# USB_Downloader.net
KiCad netlist of a schematic drawn in Altium Designer
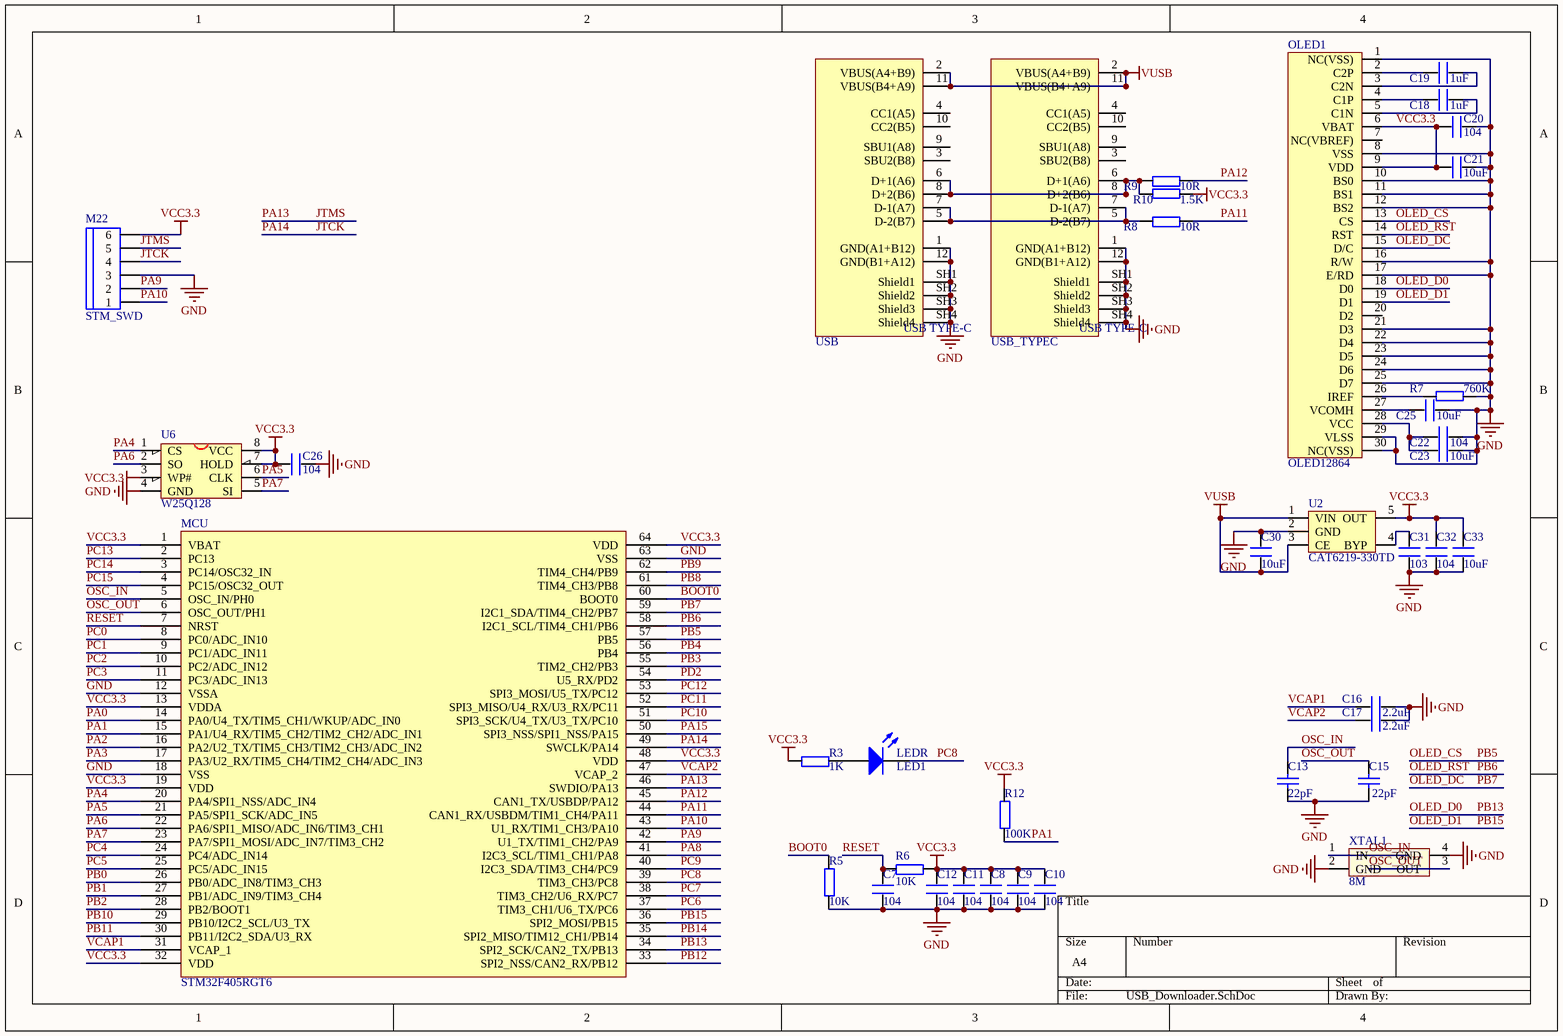
[diagram p0: USB_Downloader.SchDoc]

(export (version "E")
  (design (tool "Eeschema 10.0.6"))
  (components
    (comp (ref "C7")
      (value "104")
      (footprint "C 0603_L")
      (libsource (lib "WarShip V3 STM32103封装库") (part "C"))
    )
    (comp (ref "C8")
      (value "104")
      (footprint "C 0603_L")
      (libsource (lib "WarShip V3 STM32103封装库") (part "C"))
    )
    (comp (ref "C9")
      (value "104")
      (footprint "C 0603_L")
      (libsource (lib "WarShip V3 STM32103封装库") (part "C"))
    )
    (comp (ref "C10")
      (value "104")
      (footprint "C 0603_L")
      (libsource (lib "WarShip V3 STM32103封装库") (part "C"))
    )
    (comp (ref "C11")
      (value "104")
      (footprint "C 0603_L")
      (libsource (lib "WarShip V3 STM32103封装库") (part "C"))
    )
    (comp (ref "C12")
      (value "104")
      (footprint "C 0603_L")
      (libsource (lib "WarShip V3 STM32103封装库") (part "C"))
    )
    (comp (ref "C13") (value "22pF") (footprint "C 0603_L") (libsource (lib "L476") (part "CAP")))
    (comp (ref "C15") (value "22pF") (footprint "C 0603_L") (libsource (lib "L476") (part "CAP")))
    (comp (ref "C16")
      (value "2.2uF")
      (footprint "C 0603_L")
      (libsource (lib "WarShip V3 STM32103封装库") (part "C"))
    )
    (comp (ref "C17")
      (value "2.2uF")
      (footprint "C 0603_L")
      (libsource (lib "WarShip V3 STM32103封装库") (part "C"))
    )
    (comp (ref "C18")
      (value "1uF")
      (footprint "C 0603_L")
      (libsource (lib "WarShip V3 STM32103封装库") (part "C"))
    )
    (comp (ref "C19")
      (value "1uF")
      (footprint "C 0603_L")
      (libsource (lib "WarShip V3 STM32103封装库") (part "C"))
    )
    (comp (ref "C20")
      (value "104")
      (footprint "C 0603_L")
      (libsource (lib "WarShip V3 STM32103封装库") (part "C"))
    )
    (comp (ref "C21")
      (value "10uF")
      (footprint "C 0603_L")
      (libsource (lib "WarShip V3 STM32103封装库") (part "C"))
    )
    (comp (ref "C22")
      (value "104")
      (footprint "C 0603_L")
      (libsource (lib "WarShip V3 STM32103封装库") (part "C"))
    )
    (comp (ref "C23")
      (value "10uF")
      (footprint "C 0603_L")
      (libsource (lib "WarShip V3 STM32103封装库") (part "C"))
    )
    (comp (ref "C25")
      (value "10uF")
      (footprint "C 0603_L")
      (libsource (lib "WarShip V3 STM32103封装库") (part "C"))
    )
    (comp (ref "C26")
      (value "104")
      (footprint "C 0603_L")
      (libsource (lib "WarShip V3 STM32103封装库") (part "C"))
    )
    (comp (ref "C30")
      (value "10uF")
      (footprint "C 0603_L")
      (libsource (lib "WarShip V3 STM32103封装库") (part "C"))
    )
    (comp (ref "C31")
      (value "103")
      (footprint "C 0603_L")
      (libsource (lib "WarShip V3 STM32103封装库") (part "C"))
    )
    (comp (ref "C32")
      (value "104")
      (footprint "C 0603_L")
      (libsource (lib "WarShip V3 STM32103封装库") (part "C"))
    )
    (comp (ref "C33")
      (value "10uF")
      (footprint "C 0603_L")
      (libsource (lib "WarShip V3 STM32103封装库") (part "C"))
    )
    (comp (ref "LEDR")
      (value "LED1")
      (footprint "LED 0805B")
      (description "Typical RED, GREEN, YELLOW, AMBER GaAs LED")
      (fields (field (name "PUBLISHER") "Altium Limited"))
      (libsource (lib "阿波罗STM32F4&F7底板封装库") (part "LED2"))
    )
    (comp (ref "M22") (value "STM_SWD") (footprint "SH1.0-6P") (libsource (lib "MiniFly ") (part "HEAD6")))
    (comp (ref "MCU")
      (value "STM32F405RGT6")
      (footprint "LQFP64 10X10_L")
      (description "Flaah:256/RAM:48/IO:51")
      (libsource (lib "ATKF405 V1.1") (part "STM32F405RGT6"))
    )
    (comp (ref "OLED1")
      (value "OLED12864")
      (footprint "OLED_0.96")
      (libsource (lib "OLED模块封装库") (part "OLED12864"))
    )
    (comp (ref "R3")
      (value "1K")
      (footprint "R 0603_L")
      (libsource (lib "WarShip V3 STM32103封装库") (part "R"))
    )
    (comp (ref "R5")
      (value "10K")
      (footprint "R 0603_L")
      (libsource (lib "WarShip V3 STM32103封装库") (part "R"))
    )
    (comp (ref "R6")
      (value "10K")
      (footprint "R 0603_L")
      (libsource (lib "WarShip V3 STM32103封装库") (part "R"))
    )
    (comp (ref "R7")
      (value "760K")
      (footprint "R 0603_L")
      (libsource (lib "WarShip V3 STM32103封装库") (part "R"))
    )
    (comp (ref "R8")
      (value "10R")
      (footprint "R 0603_L")
      (libsource (lib "WarShip V3 STM32103封装库") (part "R"))
    )
    (comp (ref "R9")
      (value "10R")
      (footprint "R 0603_L")
      (libsource (lib "WarShip V3 STM32103封装库") (part "R"))
    )
    (comp (ref "R10")
      (value "1.5K")
      (footprint "R 0603_L")
      (libsource (lib "WarShip V3 STM32103封装库") (part "R"))
    )
    (comp (ref "R12")
      (value "100K")
      (footprint "R 0603_L")
      (libsource (lib "WarShip V3 STM32103封装库") (part "R"))
    )
    (comp (ref "U2")
      (value "CAT6219-330TD")
      (footprint "SOT23-5L")
      (description "3.3V 500mA LDO")
      (libsource (lib "STM32H743核心板封装库") (part "CAT6219-330TD"))
    )
    (comp (ref "U6")
      (value "W25Q128")
      (footprint "SOP8W_L")
      (description "W25X16;SST25VF016;MX25L1605")
      (libsource (lib "WarShip V3 STM32103封装库") (part "W25X16"))
    )
    (comp (ref "USB")
      (value "USB TypeC")
      (footprint "USB Type-C")
      (description "12P TypeC 母座")
      (libsource (lib "ESP32_Weather") (part "USB Type-C"))
    )
    (comp (ref "USB_TYPEC")
      (value "USB TypeC")
      (footprint "USB Type-C")
      (description "12P TypeC 母座")
      (libsource (lib "ESP32_Weather") (part "USB Type-C"))
    )
    (comp (ref "XTAL1")
      (value "8M")
      (footprint "XTAL3225   无源")
      (description "无源贴片晶振")
      (libsource (lib "REMOTOR") (part "XTAL-无源贴片"))
    )
  )
  (nets
    (net (code "1") (name "/BOOT0") (class "Default")
      (node (ref "MCU") (pin "60") (pinfunction "BOOT0_60") (pintype "passive"))
      (node (ref "R5") (pin "2") (pintype "passive"))
    )
    (net (code "2") (name "/JTCK") (class "Default")
      (node (ref "M22") (pin "4") (pinfunction "4_4") (pintype "passive"))
      (node (ref "MCU") (pin "49") (pinfunction "SWCLK/PA14_49") (pintype "passive"))
    )
    (net (code "3") (name "/JTMS") (class "Default")
      (node (ref "M22") (pin "5") (pinfunction "5_5") (pintype "passive"))
      (node (ref "MCU") (pin "46") (pinfunction "SWDIO/PA13_46") (pintype "passive"))
    )
    (net (code "4") (name "/OLED_CS") (class "Default")
      (node (ref "MCU") (pin "57") (pinfunction "PB5_57") (pintype "passive"))
      (node (ref "OLED1") (pin "13") (pinfunction "CS_13") (pintype "passive"))
    )
    (net (code "5") (name "/OLED_D0") (class "Default")
      (node (ref "MCU") (pin "34") (pinfunction "SPI2_SCK/CAN2_TX/PB13_34") (pintype "passive"))
      (node (ref "OLED1") (pin "18") (pinfunction "D0_18") (pintype "passive"))
    )
    (net (code "6") (name "/OLED_D1") (class "Default")
      (node (ref "MCU") (pin "36") (pinfunction "SPI2_MOSI/PB15_36") (pintype "passive"))
      (node (ref "OLED1") (pin "19") (pinfunction "D1_19") (pintype "passive"))
    )
    (net (code "7") (name "/OLED_DC") (class "Default")
      (node (ref "MCU") (pin "59") (pinfunction "I2C1_SDA/TIM4_CH2/PB7_59") (pintype "passive"))
      (node (ref "OLED1") (pin "15") (pinfunction "D/C_15") (pintype "passive"))
    )
    (net (code "8") (name "/OLED_RST") (class "Default")
      (node (ref "MCU") (pin "58") (pinfunction "I2C1_SCL/TIM4_CH1/PB6_58") (pintype "passive"))
      (node (ref "OLED1") (pin "14") (pinfunction "RST_14") (pintype "passive"))
    )
    (net (code "9") (name "/OSC_IN") (class "Default")
      (node (ref "C13") (pin "2") (pinfunction "2_2") (pintype "passive"))
      (node (ref "MCU") (pin "5") (pinfunction "OSC_IN/PH0_5") (pintype "passive"))
      (node (ref "XTAL1") (pin "1") (pinfunction "IN_1") (pintype "passive"))
    )
    (net (code "10") (name "/OSC_OUT") (class "Default")
      (node (ref "C15") (pin "2") (pinfunction "2_2") (pintype "passive"))
      (node (ref "MCU") (pin "6") (pinfunction "OSC_OUT/PH1_6") (pintype "passive"))
      (node (ref "XTAL1") (pin "3") (pinfunction "OUT_3") (pintype "passive"))
    )
    (net (code "11") (name "/PA0") (class "Default")
      (node (ref "MCU") (pin "14") (pinfunction "PA0/U4_TX/TIM5_CH1/WKUP/ADC_IN0_14") (pintype "passive"))
    )
    (net (code "12") (name "/PA1") (class "Default")
      (node (ref "MCU") (pin "15") (pinfunction "PA1/U4_RX/TIM5_CH2/TIM2_CH2/ADC_IN1_15") (pintype "passive"))
      (node (ref "R12") (pin "1") (pintype "passive"))
    )
    (net (code "13") (name "/PA2") (class "Default")
      (node (ref "MCU") (pin "16") (pinfunction "PA2/U2_TX/TIM5_CH3/TIM2_CH3/ADC_IN2_16") (pintype "passive"))
    )
    (net (code "14") (name "/PA3") (class "Default")
      (node (ref "MCU") (pin "17") (pinfunction "PA3/U2_RX/TIM5_CH4/TIM2_CH4/ADC_IN3_17") (pintype "passive"))
    )
    (net (code "15") (name "/PA4") (class "Default")
      (node (ref "MCU") (pin "20") (pinfunction "PA4/SPI1_NSS/ADC_IN4_20") (pintype "passive"))
      (node (ref "U6") (pin "1") (pinfunction "CS_1") (pintype "passive"))
    )
    (net (code "16") (name "/PA5") (class "Default")
      (node (ref "MCU") (pin "21") (pinfunction "PA5/SPI1_SCK/ADC_IN5_21") (pintype "passive"))
      (node (ref "U6") (pin "6") (pinfunction "CLK_6") (pintype "passive"))
    )
    (net (code "17") (name "/PA6") (class "Default")
      (node (ref "MCU") (pin "22") (pinfunction "PA6/SPI1_MISO/ADC_IN6/TIM3_CH1_22") (pintype "passive"))
      (node (ref "U6") (pin "2") (pinfunction "SO_2") (pintype "passive"))
    )
    (net (code "18") (name "/PA7") (class "Default")
      (node (ref "MCU") (pin "23") (pinfunction "PA7/SPI1_MOSI/ADC_IN7/TIM3_CH2_23") (pintype "passive"))
      (node (ref "U6") (pin "5") (pinfunction "SI_5") (pintype "passive"))
    )
    (net (code "19") (name "/PA8") (class "Default")
      (node (ref "MCU") (pin "41") (pinfunction "I2C3_SCL/TIM1_CH1/PA8_41") (pintype "passive"))
    )
    (net (code "20") (name "/PA9") (class "Default")
      (node (ref "M22") (pin "2") (pinfunction "2_2") (pintype "passive"))
      (node (ref "MCU") (pin "42") (pinfunction "U1_TX/TIM1_CH2/PA9_42") (pintype "passive"))
    )
    (net (code "21") (name "/PA10") (class "Default")
      (node (ref "M22") (pin "1") (pinfunction "1_1") (pintype "passive"))
      (node (ref "MCU") (pin "43") (pinfunction "U1_RX/TIM1_CH3/PA10_43") (pintype "passive"))
    )
    (net (code "22") (name "/PA11") (class "Default")
      (node (ref "MCU") (pin "44") (pinfunction "CAN1_RX/USBDM/TIM1_CH4/PA11_44") (pintype "passive"))
      (node (ref "R8") (pin "2") (pintype "passive"))
    )
    (net (code "23") (name "/PA12") (class "Default")
      (node (ref "MCU") (pin "45") (pinfunction "CAN1_TX/USBDP/PA12_45") (pintype "passive"))
      (node (ref "R9") (pin "2") (pintype "passive"))
    )
    (net (code "24") (name "/PA15") (class "Default")
      (node (ref "MCU") (pin "50") (pinfunction "SPI3_NSS/SPI1_NSS/PA15_50") (pintype "passive"))
    )
    (net (code "25") (name "/PB0") (class "Default")
      (node (ref "MCU") (pin "26") (pinfunction "PB0/ADC_IN8/TIM3_CH3_26") (pintype "passive"))
    )
    (net (code "26") (name "/PB1") (class "Default")
      (node (ref "MCU") (pin "27") (pinfunction "PB1/ADC_IN9/TIM3_CH4_27") (pintype "passive"))
    )
    (net (code "27") (name "/PB2") (class "Default")
      (node (ref "MCU") (pin "28") (pinfunction "PB2/BOOT1_28") (pintype "passive"))
    )
    (net (code "28") (name "/PB3") (class "Default")
      (node (ref "MCU") (pin "55") (pinfunction "TIM2_CH2/PB3_55") (pintype "passive"))
    )
    (net (code "29") (name "/PB4") (class "Default")
      (node (ref "MCU") (pin "56") (pinfunction "PB4_56") (pintype "passive"))
    )
    (net (code "30") (name "/PB8") (class "Default")
      (node (ref "MCU") (pin "61") (pinfunction "TIM4_CH3/PB8_61") (pintype "passive"))
    )
    (net (code "31") (name "/PB9") (class "Default")
      (node (ref "MCU") (pin "62") (pinfunction "TIM4_CH4/PB9_62") (pintype "passive"))
    )
    (net (code "32") (name "/PB10") (class "Default")
      (node (ref "MCU") (pin "29") (pinfunction "PB10/I2C2_SCL/U3_TX_29") (pintype "passive"))
    )
    (net (code "33") (name "/PB11") (class "Default")
      (node (ref "MCU") (pin "30") (pinfunction "PB11/I2C2_SDA/U3_RX_30") (pintype "passive"))
    )
    (net (code "34") (name "/PB12") (class "Default")
      (node (ref "MCU") (pin "33") (pinfunction "SPI2_NSS/CAN2_RX/PB12_33") (pintype "passive"))
    )
    (net (code "35") (name "/PB14") (class "Default")
      (node (ref "MCU") (pin "35") (pinfunction "SPI2_MISO/TIM12_CH1/PB14_35") (pintype "passive"))
    )
    (net (code "36") (name "/PC0") (class "Default")
      (node (ref "MCU") (pin "8") (pinfunction "PC0/ADC_IN10_8") (pintype "passive"))
    )
    (net (code "37") (name "/PC1") (class "Default")
      (node (ref "MCU") (pin "9") (pinfunction "PC1/ADC_IN11_9") (pintype "passive"))
    )
    (net (code "38") (name "/PC2") (class "Default")
      (node (ref "MCU") (pin "10") (pinfunction "PC2/ADC_IN12_10") (pintype "passive"))
    )
    (net (code "39") (name "/PC3") (class "Default")
      (node (ref "MCU") (pin "11") (pinfunction "PC3/ADC_IN13_11") (pintype "passive"))
    )
    (net (code "40") (name "/PC4") (class "Default")
      (node (ref "MCU") (pin "24") (pinfunction "PC4/ADC_IN14_24") (pintype "passive"))
    )
    (net (code "41") (name "/PC5") (class "Default")
      (node (ref "MCU") (pin "25") (pinfunction "PC5/ADC_IN15_25") (pintype "passive"))
    )
    (net (code "42") (name "/PC6") (class "Default")
      (node (ref "MCU") (pin "37") (pinfunction "TIM3_CH1/U6_TX/PC6_37") (pintype "passive"))
    )
    (net (code "43") (name "/PC7") (class "Default")
      (node (ref "MCU") (pin "38") (pinfunction "TIM3_CH2/U6_RX/PC7_38") (pintype "passive"))
    )
    (net (code "44") (name "/PC8") (class "Default")
      (node (ref "LEDR") (pin "2") (pinfunction "K_2") (pintype "passive"))
      (node (ref "MCU") (pin "39") (pinfunction "TIM3_CH3/PC8_39") (pintype "passive"))
    )
    (net (code "45") (name "/PC9") (class "Default")
      (node (ref "MCU") (pin "40") (pinfunction "I2C3_SDA/TIM3_CH4/PC9_40") (pintype "passive"))
    )
    (net (code "46") (name "/PC10") (class "Default")
      (node (ref "MCU") (pin "51") (pinfunction "SPI3_SCK/U4_TX/U3_TX/PC10_51") (pintype "passive"))
    )
    (net (code "47") (name "/PC11") (class "Default")
      (node (ref "MCU") (pin "52") (pinfunction "SPI3_MISO/U4_RX/U3_RX/PC11_52") (pintype "passive"))
    )
    (net (code "48") (name "/PC12") (class "Default")
      (node (ref "MCU") (pin "53") (pinfunction "SPI3_MOSI/U5_TX/PC12_53") (pintype "passive"))
    )
    (net (code "49") (name "/PC13") (class "Default")
      (node (ref "MCU") (pin "2") (pinfunction "PC13_2") (pintype "passive"))
    )
    (net (code "50") (name "/PC14") (class "Default")
      (node (ref "MCU") (pin "3") (pinfunction "PC14/OSC32_IN_3") (pintype "passive"))
    )
    (net (code "51") (name "/PC15") (class "Default")
      (node (ref "MCU") (pin "4") (pinfunction "PC15/OSC32_OUT_4") (pintype "passive"))
    )
    (net (code "52") (name "/PD2") (class "Default")
      (node (ref "MCU") (pin "54") (pinfunction "U5_RX/PD2_54") (pintype "passive"))
    )
    (net (code "53") (name "/RESET") (class "Default")
      (node (ref "C7") (pin "2") (pintype "passive"))
      (node (ref "MCU") (pin "7") (pinfunction "NRST_7") (pintype "passive"))
      (node (ref "R6") (pin "1") (pintype "passive"))
    )
    (net (code "54") (name "/VCAP1") (class "Default")
      (node (ref "C16") (pin "2") (pintype "passive"))
      (node (ref "MCU") (pin "31") (pinfunction "VCAP_1_31") (pintype "passive"))
    )
    (net (code "55") (name "/VCAP2") (class "Default")
      (node (ref "C17") (pin "2") (pintype "passive"))
      (node (ref "MCU") (pin "47") (pinfunction "VCAP_2_47") (pintype "passive"))
    )
    (net (code "56") (name "GND") (class "Default")
      (node (ref "C10") (pin "1") (pintype "passive"))
      (node (ref "C11") (pin "1") (pintype "passive"))
      (node (ref "C12") (pin "1") (pintype "passive"))
      (node (ref "C13") (pin "1") (pinfunction "1_1") (pintype "passive"))
      (node (ref "C15") (pin "1") (pinfunction "1_1") (pintype "passive"))
      (node (ref "C16") (pin "1") (pintype "passive"))
      (node (ref "C17") (pin "1") (pintype "passive"))
      (node (ref "C20") (pin "1") (pintype "passive"))
      (node (ref "C21") (pin "1") (pintype "passive"))
      (node (ref "C22") (pin "1") (pintype "passive"))
      (node (ref "C23") (pin "1") (pintype "passive"))
      (node (ref "C25") (pin "1") (pintype "passive"))
      (node (ref "C26") (pin "2") (pintype "passive"))
      (node (ref "C30") (pin "2") (pintype "passive"))
      (node (ref "C31") (pin "1") (pintype "passive"))
      (node (ref "C32") (pin "1") (pintype "passive"))
      (node (ref "C33") (pin "1") (pintype "passive"))
      (node (ref "C7") (pin "1") (pintype "passive"))
      (node (ref "C8") (pin "1") (pintype "passive"))
      (node (ref "C9") (pin "1") (pintype "passive"))
      (node (ref "M22") (pin "3") (pinfunction "3_3") (pintype "passive"))
      (node (ref "MCU") (pin "12") (pinfunction "VSSA_12") (pintype "passive"))
      (node (ref "MCU") (pin "18") (pinfunction "VSS_18") (pintype "passive"))
      (node (ref "MCU") (pin "63") (pinfunction "VSS_63") (pintype "passive"))
      (node (ref "OLED1") (pin "1") (pinfunction "NC(VSS)_1") (pintype "passive"))
      (node (ref "OLED1") (pin "10") (pinfunction "BS0_10") (pintype "passive"))
      (node (ref "OLED1") (pin "11") (pinfunction "BS1_11") (pintype "passive"))
      (node (ref "OLED1") (pin "12") (pinfunction "BS2_12") (pintype "passive"))
      (node (ref "OLED1") (pin "16") (pinfunction "R/W_16") (pintype "passive"))
      (node (ref "OLED1") (pin "17") (pinfunction "E/RD_17") (pintype "passive"))
      (node (ref "OLED1") (pin "21") (pinfunction "D3_21") (pintype "passive"))
      (node (ref "OLED1") (pin "22") (pinfunction "D4_22") (pintype "passive"))
      (node (ref "OLED1") (pin "23") (pinfunction "D5_23") (pintype "passive"))
      (node (ref "OLED1") (pin "24") (pinfunction "D6_24") (pintype "passive"))
      (node (ref "OLED1") (pin "25") (pinfunction "D7_25") (pintype "passive"))
      (node (ref "OLED1") (pin "29") (pinfunction "VLSS_29") (pintype "passive"))
      (node (ref "OLED1") (pin "30") (pinfunction "NC(VSS)_30") (pintype "passive"))
      (node (ref "OLED1") (pin "8") (pinfunction "VSS_8") (pintype "passive"))
      (node (ref "R5") (pin "1") (pintype "passive"))
      (node (ref "R7") (pin "1") (pintype "passive"))
      (node (ref "U2") (pin "2") (pinfunction "GND_2") (pintype "passive"))
      (node (ref "U6") (pin "4") (pinfunction "GND_4") (pintype "passive"))
      (node (ref "USB") (pin "1") (pinfunction "GND(A1+B12)_1") (pintype "passive"))
      (node (ref "USB") (pin "12") (pinfunction "GND(B1+A12)_12") (pintype "passive"))
      (node (ref "USB") (pin "SH1") (pinfunction "Shield1_SH1") (pintype "passive"))
      (node (ref "USB") (pin "SH2") (pinfunction "Shield2_SH2") (pintype "passive"))
      (node (ref "USB") (pin "SH3") (pinfunction "Shield3_SH3") (pintype "passive"))
      (node (ref "USB") (pin "SH4") (pinfunction "Shield4_SH4") (pintype "passive"))
      (node (ref "USB_TYPEC") (pin "1") (pinfunction "GND(A1+B12)_1") (pintype "passive"))
      (node (ref "USB_TYPEC") (pin "12") (pinfunction "GND(B1+A12)_12") (pintype "passive"))
      (node (ref "USB_TYPEC") (pin "SH1") (pinfunction "Shield1_SH1") (pintype "passive"))
      (node (ref "USB_TYPEC") (pin "SH2") (pinfunction "Shield2_SH2") (pintype "passive"))
      (node (ref "USB_TYPEC") (pin "SH3") (pinfunction "Shield3_SH3") (pintype "passive"))
      (node (ref "USB_TYPEC") (pin "SH4") (pinfunction "Shield4_SH4") (pintype "passive"))
      (node (ref "XTAL1") (pin "2") (pinfunction "GND_2") (pintype "passive"))
      (node (ref "XTAL1") (pin "4") (pinfunction "GND_4") (pintype "passive"))
    )
    (net (code "57") (name "Net-(LEDR-A)") (class "Default")
      (node (ref "LEDR") (pin "1") (pinfunction "A_1") (pintype "passive"))
      (node (ref "R3") (pin "2") (pintype "passive"))
    )
    (net (code "58") (name "Net-(OLED1-C1N)") (class "Default")
      (node (ref "C18") (pin "1") (pintype "passive"))
      (node (ref "OLED1") (pin "5") (pinfunction "C1N_5") (pintype "passive"))
    )
    (net (code "59") (name "Net-(OLED1-C1P)") (class "Default")
      (node (ref "C18") (pin "2") (pintype "passive"))
      (node (ref "OLED1") (pin "4") (pinfunction "C1P_4") (pintype "passive"))
    )
    (net (code "60") (name "Net-(OLED1-C2N)") (class "Default")
      (node (ref "C19") (pin "1") (pintype "passive"))
      (node (ref "OLED1") (pin "3") (pinfunction "C2N_3") (pintype "passive"))
    )
    (net (code "61") (name "Net-(OLED1-C2P)") (class "Default")
      (node (ref "C19") (pin "2") (pintype "passive"))
      (node (ref "OLED1") (pin "2") (pinfunction "C2P_2") (pintype "passive"))
    )
    (net (code "62") (name "Net-(OLED1-IREF)") (class "Default")
      (node (ref "OLED1") (pin "26") (pinfunction "IREF_26") (pintype "passive"))
      (node (ref "R7") (pin "2") (pintype "passive"))
    )
    (net (code "63") (name "Net-(OLED1-VCC)") (class "Default")
      (node (ref "C22") (pin "2") (pintype "passive"))
      (node (ref "C23") (pin "2") (pintype "passive"))
      (node (ref "OLED1") (pin "28") (pinfunction "VCC_28") (pintype "passive"))
    )
    (net (code "64") (name "Net-(OLED1-VCOMH)") (class "Default")
      (node (ref "C25") (pin "2") (pintype "passive"))
      (node (ref "OLED1") (pin "27") (pinfunction "VCOMH_27") (pintype "passive"))
    )
    (net (code "65") (name "Net-(U2-BYP)") (class "Default")
      (node (ref "C31") (pin "2") (pintype "passive"))
      (node (ref "U2") (pin "4") (pinfunction "BYP_4") (pintype "passive"))
    )
    (net (code "66") (name "Net-(USB-D+1(A6))") (class "Default")
      (node (ref "R10") (pin "2") (pintype "passive"))
      (node (ref "R9") (pin "1") (pintype "passive"))
      (node (ref "USB") (pin "6") (pinfunction "D+1(A6)_6") (pintype "passive"))
      (node (ref "USB") (pin "8") (pinfunction "D+2(B6)_8") (pintype "passive"))
      (node (ref "USB_TYPEC") (pin "6") (pinfunction "D+1(A6)_6") (pintype "passive"))
      (node (ref "USB_TYPEC") (pin "8") (pinfunction "D+2(B6)_8") (pintype "passive"))
    )
    (net (code "67") (name "Net-(USB-D-1(A7))") (class "Default")
      (node (ref "R8") (pin "1") (pintype "passive"))
      (node (ref "USB") (pin "5") (pinfunction "D-2(B7)_5") (pintype "passive"))
      (node (ref "USB") (pin "7") (pinfunction "D-1(A7)_7") (pintype "passive"))
      (node (ref "USB_TYPEC") (pin "5") (pinfunction "D-2(B7)_5") (pintype "passive"))
      (node (ref "USB_TYPEC") (pin "7") (pinfunction "D-1(A7)_7") (pintype "passive"))
    )
    (net (code "68") (name "VCC3.3") (class "Default")
      (node (ref "C10") (pin "2") (pintype "passive"))
      (node (ref "C11") (pin "2") (pintype "passive"))
      (node (ref "C12") (pin "2") (pintype "passive"))
      (node (ref "C20") (pin "2") (pintype "passive"))
      (node (ref "C21") (pin "2") (pintype "passive"))
      (node (ref "C26") (pin "1") (pintype "passive"))
      (node (ref "C32") (pin "2") (pintype "passive"))
      (node (ref "C33") (pin "2") (pintype "passive"))
      (node (ref "C8") (pin "2") (pintype "passive"))
      (node (ref "C9") (pin "2") (pintype "passive"))
      (node (ref "M22") (pin "6") (pinfunction "6_6") (pintype "passive"))
      (node (ref "MCU") (pin "1") (pinfunction "VBAT_1") (pintype "passive"))
      (node (ref "MCU") (pin "13") (pinfunction "VDDA_13") (pintype "passive"))
      (node (ref "MCU") (pin "19") (pinfunction "VDD_19") (pintype "passive"))
      (node (ref "MCU") (pin "32") (pinfunction "VDD_32") (pintype "passive"))
      (node (ref "MCU") (pin "48") (pinfunction "VDD_48") (pintype "passive"))
      (node (ref "MCU") (pin "64") (pinfunction "VDD_64") (pintype "passive"))
      (node (ref "OLED1") (pin "6") (pinfunction "VBAT_6") (pintype "passive"))
      (node (ref "OLED1") (pin "9") (pinfunction "VDD_9") (pintype "passive"))
      (node (ref "R10") (pin "1") (pintype "passive"))
      (node (ref "R12") (pin "2") (pintype "passive"))
      (node (ref "R3") (pin "1") (pintype "passive"))
      (node (ref "R6") (pin "2") (pintype "passive"))
      (node (ref "U2") (pin "5") (pinfunction "OUT_5") (pintype "passive"))
      (node (ref "U6") (pin "3") (pinfunction "WP#_3") (pintype "passive"))
      (node (ref "U6") (pin "7") (pinfunction "HOLD_7") (pintype "passive"))
      (node (ref "U6") (pin "8") (pinfunction "VCC_8") (pintype "passive"))
    )
    (net (code "69") (name "VUSB") (class "Default")
      (node (ref "C30") (pin "1") (pintype "passive"))
      (node (ref "U2") (pin "1") (pinfunction "VIN_1") (pintype "passive"))
      (node (ref "U2") (pin "3") (pinfunction "CE_3") (pintype "passive"))
      (node (ref "USB") (pin "11") (pinfunction "VBUS(B4+A9)_11") (pintype "passive"))
      (node (ref "USB") (pin "2") (pinfunction "VBUS(A4+B9)_2") (pintype "passive"))
      (node (ref "USB_TYPEC") (pin "11") (pinfunction "VBUS(B4+A9)_11") (pintype "passive"))
      (node (ref "USB_TYPEC") (pin "2") (pinfunction "VBUS(A4+B9)_2") (pintype "passive"))
    )
    (net (code "70") (name "unconnected-(OLED1-D2-Pad20)") (class "Default")
      (node (ref "OLED1") (pin "20") (pinfunction "D2_20") (pintype "passive"))
    )
    (net (code "71") (name "unconnected-(OLED1-NC(VBREF)-Pad7)") (class "Default")
      (node (ref "OLED1") (pin "7") (pinfunction "NC(VBREF)_7") (pintype "passive"))
    )
    (net (code "72") (name "unconnected-(USB-CC1(A5)-Pad4)") (class "Default")
      (node (ref "USB") (pin "4") (pinfunction "CC1(A5)_4") (pintype "passive"))
    )
    (net (code "73") (name "unconnected-(USB-CC2(B5)-Pad10)") (class "Default")
      (node (ref "USB") (pin "10") (pinfunction "CC2(B5)_10") (pintype "passive"))
    )
    (net (code "74") (name "unconnected-(USB-SBU1(A8)-Pad9)") (class "Default")
      (node (ref "USB") (pin "9") (pinfunction "SBU1(A8)_9") (pintype "passive"))
    )
    (net (code "75") (name "unconnected-(USB-SBU2(B8)-Pad3)") (class "Default")
      (node (ref "USB") (pin "3") (pinfunction "SBU2(B8)_3") (pintype "passive"))
    )
    (net (code "76") (name "unconnected-(USB_TYPEC-CC1(A5)-Pad4)") (class "Default")
      (node (ref "USB_TYPEC") (pin "4") (pinfunction "CC1(A5)_4") (pintype "passive"))
    )
    (net (code "77") (name "unconnected-(USB_TYPEC-CC2(B5)-Pad10)") (class "Default")
      (node (ref "USB_TYPEC") (pin "10") (pinfunction "CC2(B5)_10") (pintype "passive"))
    )
    (net (code "78") (name "unconnected-(USB_TYPEC-SBU1(A8)-Pad9)") (class "Default")
      (node (ref "USB_TYPEC") (pin "9") (pinfunction "SBU1(A8)_9") (pintype "passive"))
    )
    (net (code "79") (name "unconnected-(USB_TYPEC-SBU2(B8)-Pad3)") (class "Default")
      (node (ref "USB_TYPEC") (pin "3") (pinfunction "SBU2(B8)_3") (pintype "passive"))
    )
  )
)
